# NAND.net
KiCad netlist of a schematic drawn in EAGLE
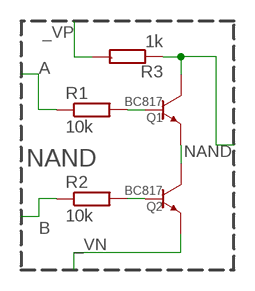
[diagram p0: schematic, sheet 1]

(export (version "E")
  (design (tool "Eeschema 10.0.6"))
  (components
    (comp (ref "Q1")
      (value "BC817")
      (footprint "eagle-import:SOT23")
      (libsource (lib "eagle-import") (part "TRANSISTOR-NPN-GENERIC-SOT23-BECDEFAULT"))
    )
    (comp (ref "Q2")
      (value "BC817")
      (footprint "eagle-import:SOT23")
      (libsource (lib "eagle-import") (part "TRANSISTOR-NPN-GENERIC-SOT23-BECDEFAULT"))
    )
    (comp (ref "R1")
      (value "10k")
      (footprint "eagle-import:R0603")
      (libsource (lib "eagle-import") (part "R-EU_R0603"))
    )
    (comp (ref "R2")
      (value "10k")
      (footprint "eagle-import:R0603")
      (libsource (lib "eagle-import") (part "R-EU_R0603"))
    )
    (comp (ref "R3")
      (value "1k")
      (footprint "eagle-import:R0603-MARK")
      (libsource (lib "eagle-import") (part "R-EU-MARKEDR0603"))
    )
  )
  (nets
    (net (code "1") (name "/A") (class "Default")
      (node (ref "R1") (pin "1") (pinfunction "1_1") (pintype "passive"))
    )
    (net (code "2") (name "/B") (class "Default")
      (node (ref "R2") (pin "1") (pinfunction "1_1") (pintype "passive"))
    )
    (net (code "3") (name "/NAND") (class "Default")
      (node (ref "Q1") (pin "P$3") (pinfunction "COLLECTOR_P$3") (pintype "bidirectional"))
      (node (ref "R3") (pin "1") (pinfunction "1_1") (pintype "passive"))
    )
    (net (code "4") (name "/_VN") (class "Default")
      (node (ref "Q2") (pin "P$2") (pinfunction "EMITTER_P$2") (pintype "bidirectional"))
    )
    (net (code "5") (name "/_VP") (class "Default")
      (node (ref "R3") (pin "2") (pinfunction "2_2") (pintype "passive"))
    )
    (net (code "6") (name "Net-(Q1-BASE)") (class "Default")
      (node (ref "Q1") (pin "P$1") (pinfunction "BASE_P$1") (pintype "bidirectional"))
      (node (ref "R1") (pin "2") (pinfunction "2_2") (pintype "passive"))
    )
    (net (code "7") (name "Net-(Q1-EMITTER)") (class "Default")
      (node (ref "Q1") (pin "P$2") (pinfunction "EMITTER_P$2") (pintype "bidirectional"))
      (node (ref "Q2") (pin "P$3") (pinfunction "COLLECTOR_P$3") (pintype "bidirectional"))
    )
    (net (code "8") (name "Net-(Q2-BASE)") (class "Default")
      (node (ref "Q2") (pin "P$1") (pinfunction "BASE_P$1") (pintype "bidirectional"))
      (node (ref "R2") (pin "2") (pinfunction "2_2") (pintype "passive"))
    )
  )
)
